# AM437x_GP_EVM_PMconnect.net
KiCad netlist of a schematic drawn in Altium Designer
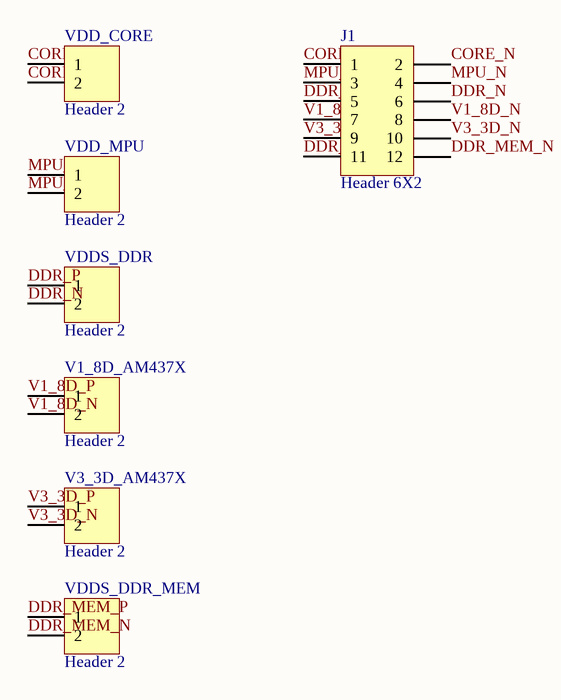
[diagram p0: AM437x_GP_EVM_PMconnect.SchDoc]

(export (version "E")
  (design (tool "Eeschema 10.0.6"))
  (components
    (comp (ref "J1")
      (value "Header 6X2")
      (footprint "HDR2X6")
      (description "Header, 6-Pin, Dual row")
      (fields (field (name "PUBLISHER") "Altium Limited"))
      (libsource (lib "Miscellaneous Connectors") (part "Header 6X2"))
    )
    (comp (ref "V1_8D_AM437X")
      (value "Header 2")
      (footprint "HDR1X2")
      (description "Header, 2-Pin")
      (fields (field (name "PUBLISHER") "Altium Limited"))
      (libsource (lib "Miscellaneous Connectors") (part "Header 2"))
    )
    (comp (ref "V3_3D_AM437X")
      (value "Header 2")
      (footprint "HDR1X2")
      (description "Header, 2-Pin")
      (fields (field (name "PUBLISHER") "Altium Limited"))
      (libsource (lib "Miscellaneous Connectors") (part "Header 2"))
    )
    (comp (ref "VDDS_DDR")
      (value "Header 2")
      (footprint "HDR1X2")
      (description "Header, 2-Pin")
      (fields (field (name "PUBLISHER") "Altium Limited"))
      (libsource (lib "Miscellaneous Connectors") (part "Header 2"))
    )
    (comp (ref "VDDS_DDR_MEM")
      (value "Header 2")
      (footprint "HDR1X2")
      (description "Header, 2-Pin")
      (fields (field (name "PUBLISHER") "Altium Limited"))
      (libsource (lib "Miscellaneous Connectors") (part "Header 2"))
    )
    (comp (ref "VDD_CORE")
      (value "Header 2")
      (footprint "HDR1X2")
      (description "Header, 2-Pin")
      (fields (field (name "PUBLISHER") "Altium Limited"))
      (libsource (lib "Miscellaneous Connectors") (part "Header 2"))
    )
    (comp (ref "VDD_MPU")
      (value "Header 2")
      (footprint "HDR1X2")
      (description "Header, 2-Pin")
      (fields (field (name "PUBLISHER") "Altium Limited"))
      (libsource (lib "Miscellaneous Connectors") (part "Header 2"))
    )
  )
  (nets
    (net (code "1") (name "/CORE_N") (class "Default")
      (node (ref "J1") (pin "2") (pinfunction "2_2") (pintype "passive"))
      (node (ref "VDD_CORE") (pin "2") (pinfunction "2_2") (pintype "passive"))
    )
    (net (code "2") (name "/CORE_P") (class "Default")
      (node (ref "J1") (pin "1") (pinfunction "1_1") (pintype "passive"))
      (node (ref "VDD_CORE") (pin "1") (pinfunction "1_1") (pintype "passive"))
    )
    (net (code "3") (name "/DDR_MEM_N") (class "Default")
      (node (ref "J1") (pin "12") (pinfunction "12_12") (pintype "passive"))
      (node (ref "VDDS_DDR_MEM") (pin "2") (pinfunction "2_2") (pintype "passive"))
    )
    (net (code "4") (name "/DDR_MEM_P") (class "Default")
      (node (ref "J1") (pin "11") (pinfunction "11_11") (pintype "passive"))
      (node (ref "VDDS_DDR_MEM") (pin "1") (pinfunction "1_1") (pintype "passive"))
    )
    (net (code "5") (name "/DDR_N") (class "Default")
      (node (ref "J1") (pin "6") (pinfunction "6_6") (pintype "passive"))
      (node (ref "VDDS_DDR") (pin "2") (pinfunction "2_2") (pintype "passive"))
    )
    (net (code "6") (name "/DDR_P") (class "Default")
      (node (ref "J1") (pin "5") (pinfunction "5_5") (pintype "passive"))
      (node (ref "VDDS_DDR") (pin "1") (pinfunction "1_1") (pintype "passive"))
    )
    (net (code "7") (name "/MPU_N") (class "Default")
      (node (ref "J1") (pin "4") (pinfunction "4_4") (pintype "passive"))
      (node (ref "VDD_MPU") (pin "2") (pinfunction "2_2") (pintype "passive"))
    )
    (net (code "8") (name "/MPU_P") (class "Default")
      (node (ref "J1") (pin "3") (pinfunction "3_3") (pintype "passive"))
      (node (ref "VDD_MPU") (pin "1") (pinfunction "1_1") (pintype "passive"))
    )
    (net (code "9") (name "/V1_8D_N") (class "Default")
      (node (ref "J1") (pin "8") (pinfunction "8_8") (pintype "passive"))
      (node (ref "V1_8D_AM437X") (pin "2") (pinfunction "2_2") (pintype "passive"))
    )
    (net (code "10") (name "/V1_8D_P") (class "Default")
      (node (ref "J1") (pin "7") (pinfunction "7_7") (pintype "passive"))
      (node (ref "V1_8D_AM437X") (pin "1") (pinfunction "1_1") (pintype "passive"))
    )
    (net (code "11") (name "/V3_3D_N") (class "Default")
      (node (ref "J1") (pin "10") (pinfunction "10_10") (pintype "passive"))
      (node (ref "V3_3D_AM437X") (pin "2") (pinfunction "2_2") (pintype "passive"))
    )
    (net (code "12") (name "/V3_3D_P") (class "Default")
      (node (ref "J1") (pin "9") (pinfunction "9_9") (pintype "passive"))
      (node (ref "V3_3D_AM437X") (pin "1") (pinfunction "1_1") (pintype "passive"))
    )
  )
)
